# AUDIO_CODEC.net
KiCad netlist of a schematic drawn in Altium Designer
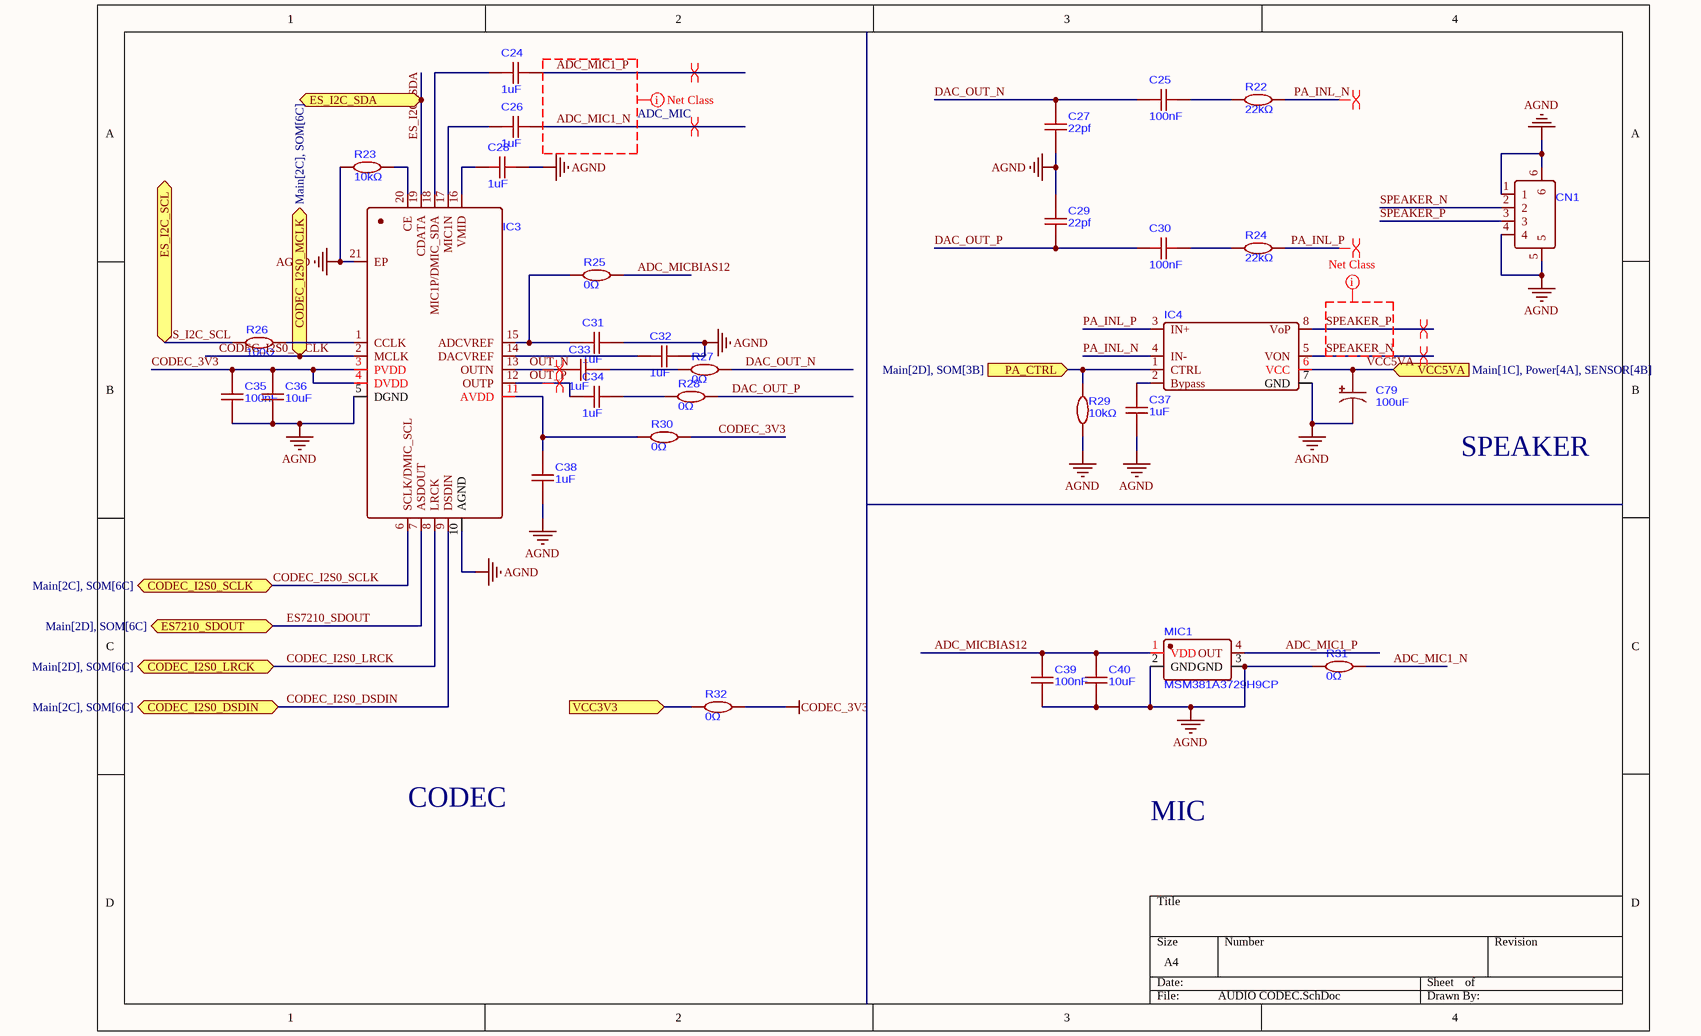
[diagram p0: AUDIO CODEC.SchDoc]

(export (version "E")
  (design (tool "Eeschema 10.0.6"))
  (components
    (comp (ref "C24")
      (value "1uF")
      (footprint "C0603")
      (description "25V 1uF X7R ±10% 0603 Ceramic Capacitors ROHS")
      (libsource (lib "Schlib2") (part "CL10B105KA8NNNC"))
    )
    (comp (ref "C25")
      (value "100nF")
      (footprint "C0603")
      (description "50V 100nF X7R ±10% 0603 Ceramic Capacitors ROHS")
      (libsource (lib "Schlib2") (part "CC0603KRX7R9BB104"))
    )
    (comp (ref "C26")
      (value "1uF")
      (footprint "C0603")
      (description "25V 1uF X7R ±10% 0603 Ceramic Capacitors ROHS")
      (libsource (lib "Schlib2") (part "CL10B105KA8NNNC"))
    )
    (comp (ref "C27")
      (value "22pf")
      (footprint "C0603")
      (description "50V 22pF C0G ±5% 0603 Ceramic Capacitors RoHS")
      (libsource (lib "Schlib2") (part "CL10C220JB8NNNC"))
    )
    (comp (ref "C28")
      (value "1uF")
      (footprint "C0603")
      (description "25V 1uF X7R ±10% 0603 Ceramic Capacitors ROHS")
      (libsource (lib "Schlib2") (part "CL10B105KA8NNNC"))
    )
    (comp (ref "C29")
      (value "22pf")
      (footprint "C0603")
      (description "50V 22pF C0G ±5% 0603 Ceramic Capacitors RoHS")
      (libsource (lib "Schlib2") (part "CL10C220JB8NNNC"))
    )
    (comp (ref "C30")
      (value "100nF")
      (footprint "C0603")
      (description "50V 100nF X7R ±10% 0603 Ceramic Capacitors ROHS")
      (libsource (lib "Schlib2") (part "CC0603KRX7R9BB104"))
    )
    (comp (ref "C31")
      (value "1uF")
      (footprint "C0603")
      (description "25V 1uF X7R ±10% 0603 Ceramic Capacitors ROHS")
      (libsource (lib "Schlib2") (part "CL10B105KA8NNNC"))
    )
    (comp (ref "C32")
      (value "1uF")
      (footprint "C0603")
      (description "25V 1uF X7R ±10% 0603 Ceramic Capacitors ROHS")
      (libsource (lib "Schlib2") (part "CL10B105KA8NNNC"))
    )
    (comp (ref "C33")
      (value "1uF")
      (footprint "C0603")
      (description "25V 1uF X7R ±10% 0603 Ceramic Capacitors ROHS")
      (libsource (lib "Schlib2") (part "CL10B105KA8NNNC"))
    )
    (comp (ref "C34")
      (value "1uF")
      (footprint "C0603")
      (description "25V 1uF X7R ±10% 0603 Ceramic Capacitors ROHS")
      (libsource (lib "Schlib2") (part "CL10B105KA8NNNC"))
    )
    (comp (ref "C35")
      (value "100nF")
      (footprint "C0603")
      (description "50V 100nF X7R ±10% 0603 Ceramic Capacitors ROHS")
      (libsource (lib "Schlib2") (part "CC0603KRX7R9BB104"))
    )
    (comp (ref "C36")
      (value "10uF")
      (footprint "C0603")
      (description "25V 10uF X5R ±20% 0603 Ceramic Capacitors ROHS")
      (libsource (lib "Schlib2") (part "CL10A106MA8NRNC"))
    )
    (comp (ref "C37")
      (value "1uF")
      (footprint "C0603")
      (description "25V 1uF X7R ±10% 0603 Ceramic Capacitors ROHS")
      (libsource (lib "Schlib2") (part "CL10B105KA8NNNC"))
    )
    (comp (ref "C38")
      (value "1uF")
      (footprint "C0603")
      (description "25V 1uF X7R ±10% 0603 Ceramic Capacitors ROHS")
      (libsource (lib "Schlib2") (part "CL10B105KA8NNNC"))
    )
    (comp (ref "C39")
      (value "100nF")
      (footprint "C0603")
      (description "50V 100nF X7R ±10% 0603 Ceramic Capacitors ROHS")
      (libsource (lib "Schlib2") (part "CC0603KRX7R9BB104"))
    )
    (comp (ref "C40")
      (value "10uF")
      (footprint "C0603")
      (description "25V 10uF X5R ±20% 0603 Ceramic Capacitors ROHS")
      (libsource (lib "Schlib2") (part "CL10A106MA8NRNC"))
    )
    (comp (ref "C79")
      (value "100uF")
      (footprint "CAP-SMD_L3.5-W2.8-R-RD")
      (description "100uF 10V ±10% CASE-B-3528-19(mm) Tantalum Capacitors RoHS")
      (libsource (lib "Schlib2") (part "CA45A-B-10V-100UF-K"))
    )
    (comp (ref "CN1")
      (value "533980471")
      (footprint "CONN-SMD_4P-P1.25_XUNPU_WAFER-GH1.25-4PWB")
      (libsource (lib "Schlib2") (part "533980471"))
    )
    (comp (ref "IC3")
      (value "Low Power Mono Audio CODEC")
      (footprint "WQFN-20_L3.0-W3.0-P0.40-BL-EP1.7")
      (description "1.8V~3.3V QFN-20-EP(3x3) Signal Switches, Multiplexers, Decoders RoHS")
      (libsource (lib "Schlib2") (part "ES8311"))
    )
    (comp (ref "IC4")
      (value "NS4150B 3.0W Mono Class-D Audio Power Amplifier")
      (footprint "MSOP-8_L3.0-W3.0-P0.65-LS5.0-BL")
      (description "4mA 1-Channel 3Wx1@4Ω Class D MSOP-8 Audio Amplifiers RoHS")
      (libsource (lib "Schlib2") (part "NS4150"))
    )
    (comp (ref "MIC1")
      (value "MSM381A3729H9CP")
      (footprint "MIC-SMD_4P-L3.8-W3.0-P2.46-S1.70-TR")
      (description "OCLGA-4(3x3.8) MEMS Microphones ROHS")
      (libsource (lib "Schlib2") (part "MSM381A3729H9CP"))
    )
    (comp (ref "R22")
      (value "22kΩ")
      (footprint "R0603")
      (description "100mW 22kΩ 75V ±100ppm/℃ Thick Film Resistor ±1% 0603 Chip Resistor - Surface Mount RoHS")
      (libsource (lib "Schlib2") (part "RC0603FR-0722KL"))
    )
    (comp (ref "R23")
      (value "10kΩ")
      (footprint "R0603")
      (description "100mW 10kΩ 75V ±100ppm/℃ Thick Film Resistor ±1% 0603 Chip Resistor - Surface Mount ROHS")
      (libsource (lib "Schlib2") (part "RC0603FR-0710KL"))
    )
    (comp (ref "R24")
      (value "22kΩ")
      (footprint "R0603")
      (description "100mW 22kΩ 75V ±100ppm/℃ Thick Film Resistor ±1% 0603 Chip Resistor - Surface Mount RoHS")
      (libsource (lib "Schlib2") (part "RC0603FR-0722KL"))
    )
    (comp (ref "R25")
      (value "0Ω")
      (footprint "R0603")
      (description "100mW 0Ω 75V Thick Film Resistor ±5% 0603 Chip Resistor - Surface Mount RoHS")
      (libsource (lib "Schlib2") (part "RC0603JR-070RL"))
    )
    (comp (ref "R26")
      (value "100Ω")
      (footprint "R0603")
      (description "100mW 100Ω 75V ±100ppm/℃ Thick Film Resistor ±1% 0603 Chip Resistor - Surface Mount ROHS")
      (libsource (lib "Schlib2") (part "RC0603FR-07100RL"))
    )
    (comp (ref "R27")
      (value "0Ω")
      (footprint "R0603")
      (description "100mW 0Ω 75V Thick Film Resistor ±5% 0603 Chip Resistor - Surface Mount RoHS")
      (libsource (lib "Schlib2") (part "RC0603JR-070RL"))
    )
    (comp (ref "R28")
      (value "0Ω")
      (footprint "R0603")
      (description "100mW 0Ω 75V Thick Film Resistor ±5% 0603 Chip Resistor - Surface Mount RoHS")
      (libsource (lib "Schlib2") (part "RC0603JR-070RL"))
    )
    (comp (ref "R29")
      (value "10kΩ")
      (footprint "R0603")
      (description "100mW 10kΩ 75V ±100ppm/℃ Thick Film Resistor ±1% 0603 Chip Resistor - Surface Mount ROHS")
      (libsource (lib "Schlib2") (part "RC0603FR-0710KL"))
    )
    (comp (ref "R30")
      (value "0Ω")
      (footprint "R0603")
      (description "100mW 0Ω 75V Thick Film Resistor ±5% 0603 Chip Resistor - Surface Mount RoHS")
      (libsource (lib "Schlib2") (part "RC0603JR-070RL"))
    )
    (comp (ref "R31")
      (value "0Ω")
      (footprint "R0603")
      (description "100mW 0Ω 75V Thick Film Resistor ±5% 0603 Chip Resistor - Surface Mount RoHS")
      (libsource (lib "Schlib2") (part "RC0603JR-070RL"))
    )
    (comp (ref "R32")
      (value "0Ω")
      (footprint "R0603")
      (description "100mW 0Ω 75V Thick Film Resistor ±5% 0603 Chip Resistor - Surface Mount RoHS")
      (libsource (lib "Schlib2") (part "RC0603JR-070RL"))
    )
  )
  (nets
    (net (code "1") (name "/ADC_MIC1_N") (class "Default")
      (node (ref "C26") (pin "1") (pinfunction "1_1") (pintype "passive"))
      (node (ref "R31") (pin "2") (pinfunction "2_2") (pintype "passive"))
    )
    (net (code "2") (name "/ADC_MIC1_P") (class "Default")
      (node (ref "C24") (pin "2") (pinfunction "2_2") (pintype "passive"))
      (node (ref "MIC1") (pin "4") (pinfunction "OUT_4") (pintype "passive"))
    )
    (net (code "3") (name "/ADC_MICBIAS12") (class "Default")
      (node (ref "C39") (pin "2") (pinfunction "2_2") (pintype "passive"))
      (node (ref "C40") (pin "2") (pinfunction "2_2") (pintype "passive"))
      (node (ref "MIC1") (pin "1") (pinfunction "VDD_1") (pintype "passive"))
      (node (ref "R25") (pin "2") (pinfunction "2_2") (pintype "passive"))
    )
    (net (code "4") (name "/CODEC_I2S0_DSDIN") (class "Default")
      (node (ref "IC3") (pin "9") (pinfunction "DSDIN_9") (pintype "passive"))
    )
    (net (code "5") (name "/CODEC_I2S0_LRCK") (class "Default")
      (node (ref "IC3") (pin "8") (pinfunction "LRCK_8") (pintype "passive"))
    )
    (net (code "6") (name "/CODEC_I2S0_MCLK") (class "Default")
      (node (ref "IC3") (pin "2") (pinfunction "MCLK_2") (pintype "passive"))
    )
    (net (code "7") (name "/CODEC_I2S0_SCLK") (class "Default")
      (node (ref "IC3") (pin "6") (pinfunction "SCLK/DMIC_SCL_6") (pintype "passive"))
    )
    (net (code "8") (name "/DAC_OUT_N") (class "Default")
      (node (ref "C25") (pin "1") (pinfunction "1_1") (pintype "passive"))
      (node (ref "C27") (pin "2") (pinfunction "2_2") (pintype "passive"))
      (node (ref "R27") (pin "2") (pinfunction "2_2") (pintype "passive"))
    )
    (net (code "9") (name "/DAC_OUT_P") (class "Default")
      (node (ref "C29") (pin "1") (pinfunction "1_1") (pintype "passive"))
      (node (ref "C30") (pin "1") (pinfunction "1_1") (pintype "passive"))
      (node (ref "R28") (pin "2") (pinfunction "2_2") (pintype "passive"))
    )
    (net (code "10") (name "/ES7210_SDOUT") (class "Default")
      (node (ref "IC3") (pin "7") (pinfunction "ASDOUT_7") (pintype "passive"))
    )
    (net (code "11") (name "/ES_I2C_SCL") (class "Default")
      (node (ref "R26") (pin "1") (pinfunction "1_1") (pintype "passive"))
    )
    (net (code "12") (name "/ES_I2C_SDA") (class "Default")
      (node (ref "IC3") (pin "19") (pinfunction "CDATA_19") (pintype "passive"))
    )
    (net (code "13") (name "/OUT_N") (class "Default")
      (node (ref "C33") (pin "2") (pinfunction "2_2") (pintype "passive"))
      (node (ref "IC3") (pin "13") (pinfunction "OUTN_13") (pintype "passive"))
    )
    (net (code "14") (name "/OUT_P") (class "Default")
      (node (ref "C34") (pin "2") (pinfunction "2_2") (pintype "passive"))
      (node (ref "IC3") (pin "12") (pinfunction "OUTP_12") (pintype "passive"))
    )
    (net (code "15") (name "/PA_CTRL") (class "Default")
      (node (ref "IC4") (pin "1") (pinfunction "CTRL_1") (pintype "passive"))
      (node (ref "R29") (pin "2") (pinfunction "2_2") (pintype "passive"))
    )
    (net (code "16") (name "/PA_INL_N") (class "Default")
      (node (ref "IC4") (pin "4") (pinfunction "IN-_4") (pintype "passive"))
      (node (ref "R22") (pin "2") (pinfunction "2_2") (pintype "passive"))
    )
    (net (code "17") (name "/PA_INL_P") (class "Default")
      (node (ref "IC4") (pin "3") (pinfunction "IN+_3") (pintype "passive"))
      (node (ref "R24") (pin "2") (pinfunction "2_2") (pintype "passive"))
    )
    (net (code "18") (name "/SPEAKER_N") (class "Default")
      (node (ref "CN1") (pin "2") (pinfunction "2_2") (pintype "passive"))
      (node (ref "IC4") (pin "5") (pinfunction "VON_5") (pintype "passive"))
    )
    (net (code "19") (name "/SPEAKER_P") (class "Default")
      (node (ref "CN1") (pin "3") (pinfunction "3_3") (pintype "passive"))
      (node (ref "IC4") (pin "8") (pinfunction "VoP_8") (pintype "passive"))
    )
    (net (code "20") (name "/VCC3V3") (class "Default")
      (node (ref "R32") (pin "1") (pinfunction "1_1") (pintype "passive"))
    )
    (net (code "21") (name "/VCC5VA") (class "Default")
      (node (ref "C79") (pin "1") (pinfunction "1_1") (pintype "passive"))
      (node (ref "IC4") (pin "6") (pinfunction "VCC_6") (pintype "passive"))
    )
    (net (code "22") (name "AGND") (class "Default")
      (node (ref "C27") (pin "1") (pinfunction "1_1") (pintype "passive"))
      (node (ref "C28") (pin "1") (pinfunction "1_1") (pintype "passive"))
      (node (ref "C29") (pin "2") (pinfunction "2_2") (pintype "passive"))
      (node (ref "C31") (pin "1") (pinfunction "1_1") (pintype "passive"))
      (node (ref "C32") (pin "1") (pinfunction "1_1") (pintype "passive"))
      (node (ref "C35") (pin "1") (pinfunction "1_1") (pintype "passive"))
      (node (ref "C36") (pin "1") (pinfunction "1_1") (pintype "passive"))
      (node (ref "C37") (pin "1") (pinfunction "1_1") (pintype "passive"))
      (node (ref "C38") (pin "2") (pinfunction "2_2") (pintype "passive"))
      (node (ref "C39") (pin "1") (pinfunction "1_1") (pintype "passive"))
      (node (ref "C40") (pin "1") (pinfunction "1_1") (pintype "passive"))
      (node (ref "C79") (pin "2") (pinfunction "2_2") (pintype "passive"))
      (node (ref "CN1") (pin "1") (pinfunction "1_1") (pintype "passive"))
      (node (ref "CN1") (pin "4") (pinfunction "4_4") (pintype "passive"))
      (node (ref "CN1") (pin "5") (pinfunction "5_5") (pintype "passive"))
      (node (ref "CN1") (pin "6") (pinfunction "6_6") (pintype "passive"))
      (node (ref "IC3") (pin "10") (pinfunction "AGND_10") (pintype "passive"))
      (node (ref "IC3") (pin "21") (pinfunction "EP_21") (pintype "passive"))
      (node (ref "IC3") (pin "5") (pinfunction "DGND_5") (pintype "passive"))
      (node (ref "IC4") (pin "7") (pinfunction "GND_7") (pintype "passive"))
      (node (ref "MIC1") (pin "2") (pinfunction "GND_2") (pintype "passive"))
      (node (ref "MIC1") (pin "3") (pinfunction "GND_3") (pintype "passive"))
      (node (ref "R23") (pin "1") (pinfunction "1_1") (pintype "passive"))
      (node (ref "R29") (pin "1") (pinfunction "1_1") (pintype "passive"))
      (node (ref "R31") (pin "1") (pinfunction "1_1") (pintype "passive"))
    )
    (net (code "23") (name "CODEC_3V3") (class "Default")
      (node (ref "C35") (pin "2") (pinfunction "2_2") (pintype "passive"))
      (node (ref "C36") (pin "2") (pinfunction "2_2") (pintype "passive"))
      (node (ref "IC3") (pin "3") (pinfunction "PVDD_3") (pintype "passive"))
      (node (ref "IC3") (pin "4") (pinfunction "DVDD_4") (pintype "passive"))
      (node (ref "R30") (pin "2") (pinfunction "2_2") (pintype "passive"))
      (node (ref "R32") (pin "2") (pinfunction "2_2") (pintype "passive"))
    )
    (net (code "24") (name "Net-(C25-Pad2)") (class "Default")
      (node (ref "C25") (pin "2") (pinfunction "2_2") (pintype "passive"))
      (node (ref "R22") (pin "1") (pinfunction "1_1") (pintype "passive"))
    )
    (net (code "25") (name "Net-(C30-Pad2)") (class "Default")
      (node (ref "C30") (pin "2") (pinfunction "2_2") (pintype "passive"))
      (node (ref "R24") (pin "1") (pinfunction "1_1") (pintype "passive"))
    )
    (net (code "26") (name "Net-(C33-Pad1)") (class "Default")
      (node (ref "C33") (pin "1") (pinfunction "1_1") (pintype "passive"))
      (node (ref "R27") (pin "1") (pinfunction "1_1") (pintype "passive"))
    )
    (net (code "27") (name "Net-(C34-Pad1)") (class "Default")
      (node (ref "C34") (pin "1") (pinfunction "1_1") (pintype "passive"))
      (node (ref "R28") (pin "1") (pinfunction "1_1") (pintype "passive"))
    )
    (net (code "28") (name "Net-(IC3-ADCVREF)") (class "Default")
      (node (ref "C31") (pin "2") (pinfunction "2_2") (pintype "passive"))
      (node (ref "IC3") (pin "15") (pinfunction "ADCVREF_15") (pintype "passive"))
      (node (ref "R25") (pin "1") (pinfunction "1_1") (pintype "passive"))
    )
    (net (code "29") (name "Net-(IC3-AVDD)") (class "Default")
      (node (ref "C38") (pin "1") (pinfunction "1_1") (pintype "passive"))
      (node (ref "IC3") (pin "11") (pinfunction "AVDD_11") (pintype "passive"))
      (node (ref "R30") (pin "1") (pinfunction "1_1") (pintype "passive"))
    )
    (net (code "30") (name "Net-(IC3-CCLK)") (class "Default")
      (node (ref "IC3") (pin "1") (pinfunction "CCLK_1") (pintype "passive"))
      (node (ref "R26") (pin "2") (pinfunction "2_2") (pintype "passive"))
    )
    (net (code "31") (name "Net-(IC3-CE)") (class "Default")
      (node (ref "IC3") (pin "20") (pinfunction "CE_20") (pintype "passive"))
      (node (ref "R23") (pin "2") (pinfunction "2_2") (pintype "passive"))
    )
    (net (code "32") (name "Net-(IC3-DACVREF)") (class "Default")
      (node (ref "C32") (pin "2") (pinfunction "2_2") (pintype "passive"))
      (node (ref "IC3") (pin "14") (pinfunction "DACVREF_14") (pintype "passive"))
    )
    (net (code "33") (name "Net-(IC3-MIC1N)") (class "Default")
      (node (ref "C26") (pin "2") (pinfunction "2_2") (pintype "passive"))
      (node (ref "IC3") (pin "17") (pinfunction "MIC1N_17") (pintype "passive"))
    )
    (net (code "34") (name "Net-(IC3-MIC1P{slash}DMIC_SDA)") (class "Default")
      (node (ref "C24") (pin "1") (pinfunction "1_1") (pintype "passive"))
      (node (ref "IC3") (pin "18") (pinfunction "MIC1P/DMIC_SDA_18") (pintype "passive"))
    )
    (net (code "35") (name "Net-(IC3-VMID)") (class "Default")
      (node (ref "C28") (pin "2") (pinfunction "2_2") (pintype "passive"))
      (node (ref "IC3") (pin "16") (pinfunction "VMID_16") (pintype "passive"))
    )
    (net (code "36") (name "Net-(IC4-Bypass)") (class "Default")
      (node (ref "C37") (pin "2") (pinfunction "2_2") (pintype "passive"))
      (node (ref "IC4") (pin "2") (pinfunction "Bypass_2") (pintype "passive"))
    )
  )
)
